# led_brick_smd.net
KiCad netlist of a schematic drawn in EAGLE
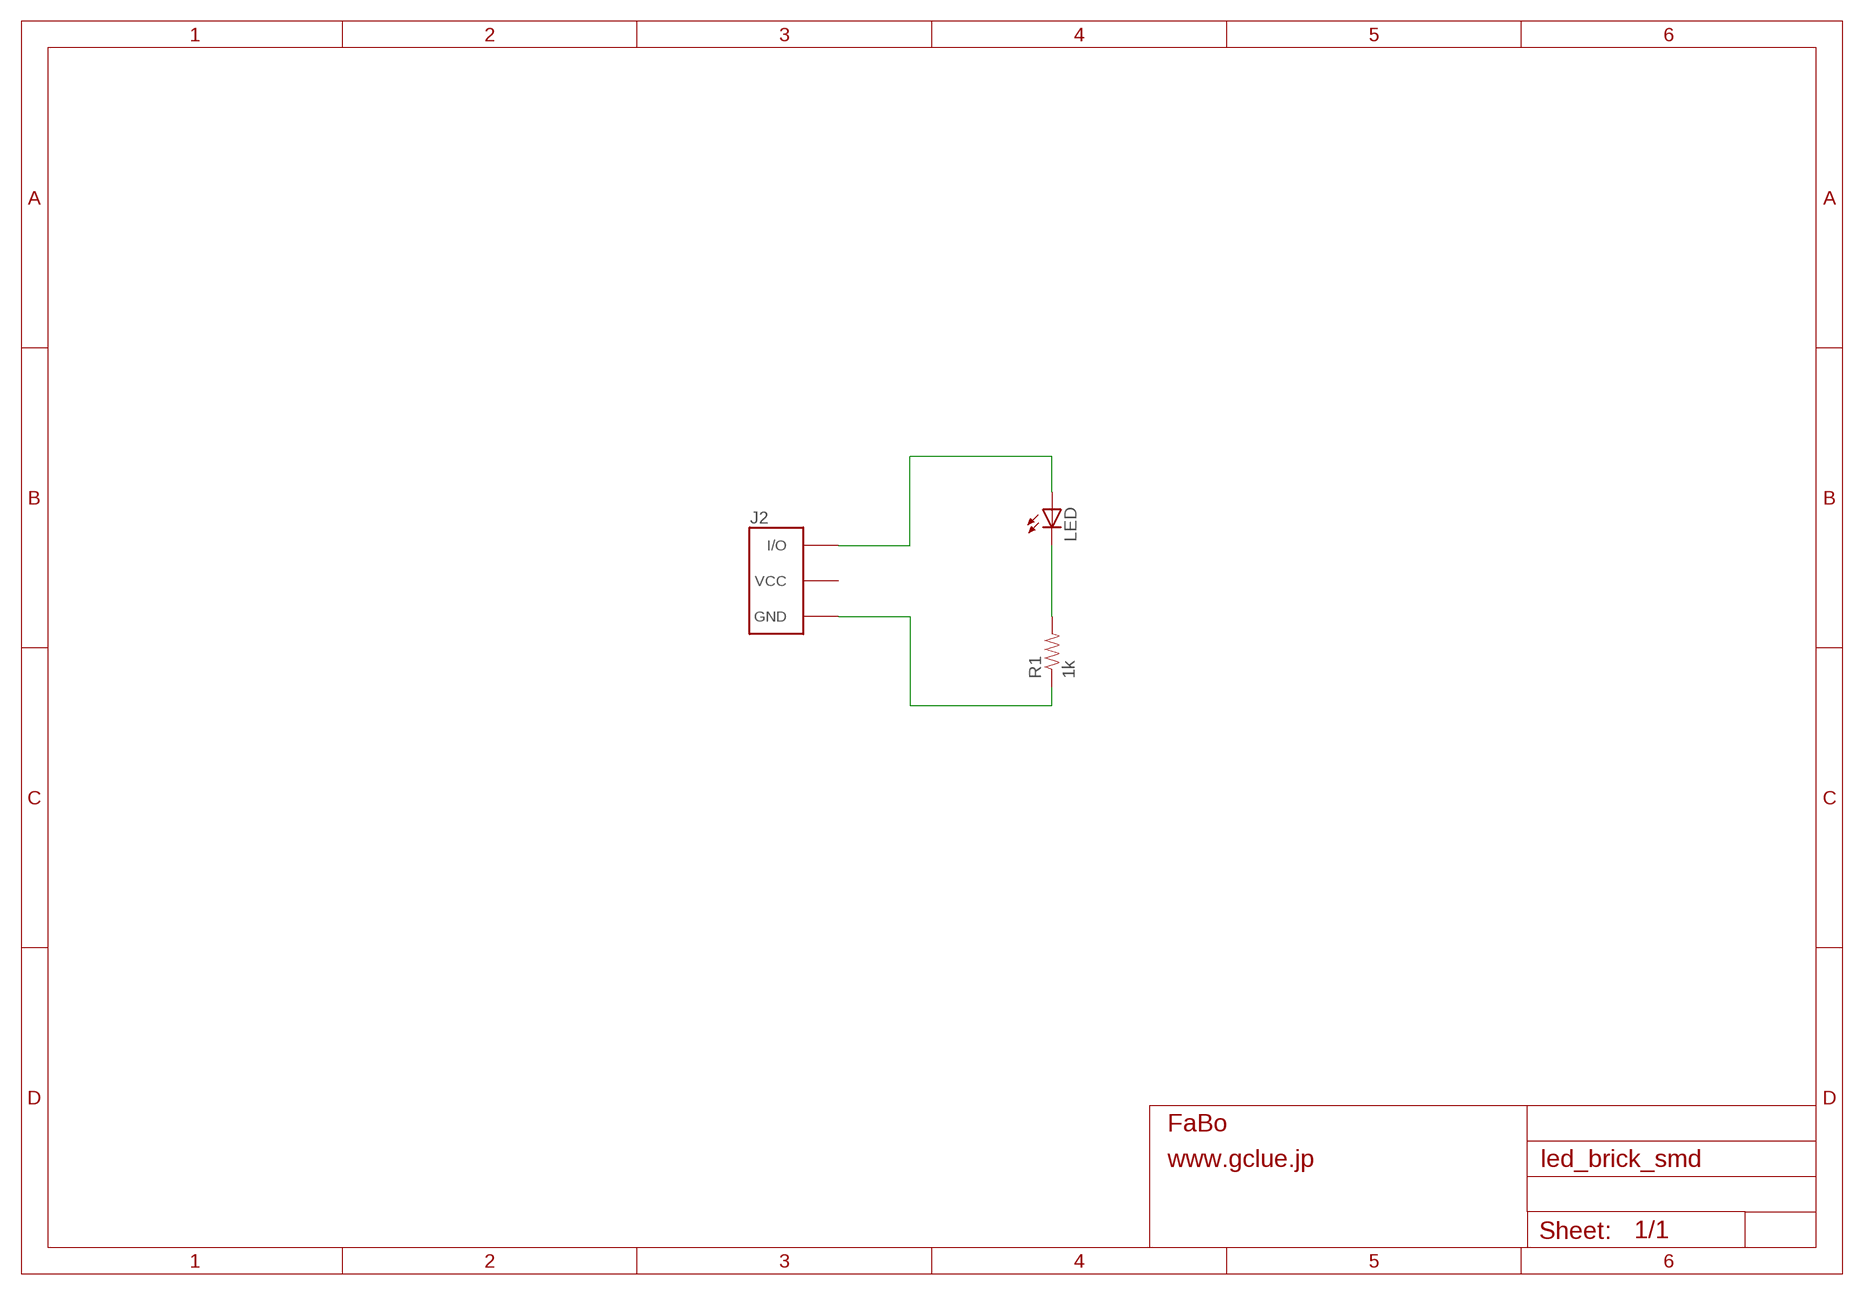
[diagram p0: schematic, sheet 1]

(export (version "E")
  (design (tool "Eeschema 10.0.6"))
  (components
    (comp (ref "J2")
      (value "BRICK_3PIN")
      (footprint "eagle-import:BRICK_3PIN")
      (libsource (lib "eagle-import") (part "BRICK_3PIN"))
    )
    (comp (ref "LED")
      (value "LED")
      (footprint "eagle-import:CHIP-LED0603")
      (libsource (lib "eagle-import") (part "LEDCHIP-LED0603"))
    )
    (comp (ref "R1")
      (value "1k")
      (footprint "eagle-import:0603-RES")
      (libsource (lib "eagle-import") (part "RESISTOR0603-RES"))
    )
  )
  (nets
    (net (code "1") (name "Net-(J2-I{slash}O)") (class "Default")
      (node (ref "J2") (pin "IN/OUT") (pinfunction "I/O_IN/OUT") (pintype "bidirectional"))
      (node (ref "LED") (pin "A") (pinfunction "A_A") (pintype "passive"))
    )
    (net (code "2") (name "Net-(J2-PadGND)") (class "Default")
      (node (ref "J2") (pin "GND") (pinfunction "GND_GND") (pintype "bidirectional"))
      (node (ref "R1") (pin "1") (pinfunction "1_1") (pintype "passive"))
    )
    (net (code "3") (name "Net-(LED-PadC)") (class "Default")
      (node (ref "LED") (pin "C") (pinfunction "C_C") (pintype "passive"))
      (node (ref "R1") (pin "2") (pinfunction "2_2") (pintype "passive"))
    )
    (net (code "4") (name "unconnected-(J2-PadVCC)") (class "Default")
      (node (ref "J2") (pin "VCC") (pinfunction "VCC_VCC") (pintype "bidirectional"))
    )
  )
)
